# Controller2019_sensorless.net
KiCad netlist of a schematic drawn in EAGLE
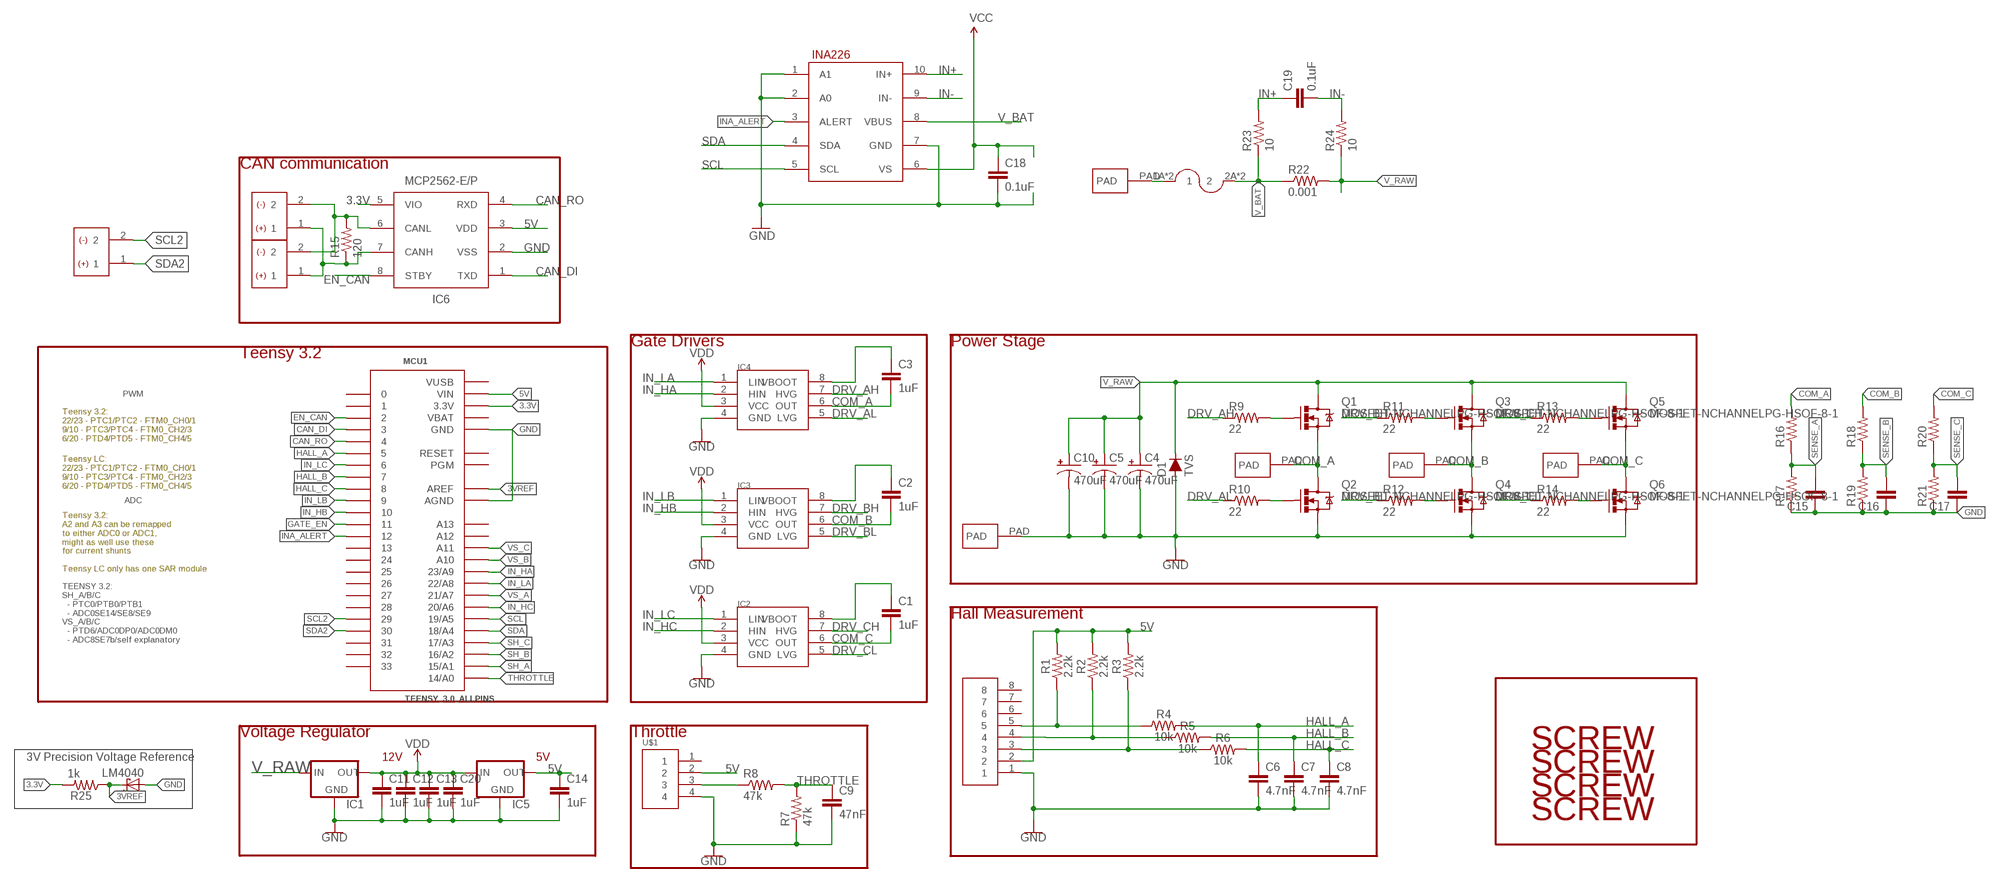
[diagram p0: schematic, sheet 1, part 1 of 2]
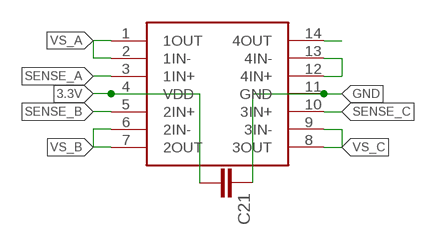
[diagram p1: schematic, sheet 1, part 2 of 2]

(export (version "E")
  (design (tool "Eeschema 10.0.6"))
  (components
    (comp (ref "C1")
      (value "1uF")
      (footprint "eagle-import:CAP-PTH-SMALL-KIT")
      (libsource (lib "eagle-import") (part "CAPKIT"))
    )
    (comp (ref "C2")
      (value "1uF")
      (footprint "eagle-import:CAP-PTH-SMALL-KIT")
      (libsource (lib "eagle-import") (part "CAPKIT"))
    )
    (comp (ref "C3")
      (value "1uF")
      (footprint "eagle-import:CAP-PTH-SMALL-KIT")
      (libsource (lib "eagle-import") (part "CAPKIT"))
    )
    (comp (ref "C4")
      (value "470uF")
      (footprint "eagle-import:CPOL-RADIAL-5MM-10MM")
      (libsource (lib "eagle-import") (part "1000UF-RADIAL-5MM-25V-20%"))
    )
    (comp (ref "C5")
      (value "470uF")
      (footprint "eagle-import:CPOL-RADIAL-5MM-10MM")
      (libsource (lib "eagle-import") (part "1000UF-RADIAL-5MM-25V-20%"))
    )
    (comp (ref "C6")
      (value "4.7nF")
      (footprint "eagle-import:0603-CAP")
      (libsource (lib "eagle-import") (part "SparkFun-Passives_CAP0603-CAP"))
    )
    (comp (ref "C7")
      (value "4.7nF")
      (footprint "eagle-import:0603-CAP")
      (libsource (lib "eagle-import") (part "SparkFun-Passives_CAP0603-CAP"))
    )
    (comp (ref "C8")
      (value "4.7nF")
      (footprint "eagle-import:0603-CAP")
      (libsource (lib "eagle-import") (part "SparkFun-Passives_CAP0603-CAP"))
    )
    (comp (ref "C9")
      (value "47nF")
      (footprint "eagle-import:0603-CAP")
      (libsource (lib "eagle-import") (part "SparkFun-Passives_CAP0603-CAP"))
    )
    (comp (ref "C10")
      (value "470uF")
      (footprint "eagle-import:CPOL-RADIAL-5MM-10MM")
      (libsource (lib "eagle-import") (part "1000UF-RADIAL-5MM-25V-20%"))
    )
    (comp (ref "C11")
      (value "1uF")
      (footprint "eagle-import:CAP-PTH-SMALL-KIT")
      (libsource (lib "eagle-import") (part "CAPKIT"))
    )
    (comp (ref "C12")
      (value "1uF")
      (footprint "eagle-import:CAP-PTH-SMALL-KIT")
      (libsource (lib "eagle-import") (part "CAPKIT"))
    )
    (comp (ref "C13")
      (value "1uF")
      (footprint "eagle-import:CAP-PTH-SMALL-KIT")
      (libsource (lib "eagle-import") (part "CAPKIT"))
    )
    (comp (ref "C14")
      (value "1uF")
      (footprint "eagle-import:CAP-PTH-SMALL-KIT")
      (libsource (lib "eagle-import") (part "CAPKIT"))
    )
    (comp (ref "C15")
      (value "CAP0603-CAP")
      (footprint "eagle-import:0603-CAP")
      (libsource (lib "eagle-import") (part "SparkFun-Passives_CAP0603-CAP"))
    )
    (comp (ref "C16")
      (value "CAP0603-CAP")
      (footprint "eagle-import:0603-CAP")
      (libsource (lib "eagle-import") (part "SparkFun-Passives_CAP0603-CAP"))
    )
    (comp (ref "C17")
      (value "CAP0603-CAP")
      (footprint "eagle-import:0603-CAP")
      (libsource (lib "eagle-import") (part "SparkFun-Passives_CAP0603-CAP"))
    )
    (comp (ref "C18")
      (value "0.1uF")
      (footprint "eagle-import:0603-CAP")
      (libsource (lib "eagle-import") (part "SparkFun-Passives_CAP0603-CAP"))
    )
    (comp (ref "C19")
      (value "0.1uF")
      (footprint "eagle-import:0603-CAP")
      (libsource (lib "eagle-import") (part "SparkFun-Passives_CAP0603-CAP"))
    )
    (comp (ref "C20")
      (value "1uF")
      (footprint "eagle-import:CAP-PTH-SMALL-KIT")
      (libsource (lib "eagle-import") (part "CAPKIT"))
    )
    (comp (ref "C21")
      (value "CAP0603-CAP")
      (footprint "eagle-import:0603-CAP")
      (libsource (lib "eagle-import") (part "SparkFun-Passives_CAP0603-CAP"))
    )
    (comp (ref "CAN1")
      (value "HEADER2")
      (footprint "eagle-import:2PINVALULOK")
      (libsource (lib "eagle-import") (part "HEADER2"))
    )
    (comp (ref "CAN2")
      (value "HEADER2")
      (footprint "eagle-import:2PINVALULOK")
      (libsource (lib "eagle-import") (part "HEADER2"))
    )
    (comp (ref "D1")
      (value "TVS")
      (footprint "eagle-import:DIODE-1N4001")
      (libsource (lib "eagle-import") (part "DIODE-PTH"))
    )
    (comp (ref "I2C")
      (value "HEADER2")
      (footprint "eagle-import:2PINVALULOK")
      (libsource (lib "eagle-import") (part "HEADER2"))
    )
    (comp (ref "IC1")
      (value "V_REG_78XX")
      (footprint "eagle-import:V78W_BACKWARDS")
      (libsource (lib "eagle-import") (part "V_REG_78XX"))
    )
    (comp (ref "IC2")
      (value "L6387EDIP8")
      (footprint "eagle-import:DIP762W53P254L1092H508Q8B")
      (libsource (lib "eagle-import") (part "L6387EDIP8"))
    )
    (comp (ref "IC3")
      (value "L6387EDIP8")
      (footprint "eagle-import:DIP762W53P254L1092H508Q8B")
      (libsource (lib "eagle-import") (part "L6387EDIP8"))
    )
    (comp (ref "IC4")
      (value "L6387EDIP8")
      (footprint "eagle-import:DIP762W53P254L1092H508Q8B")
      (libsource (lib "eagle-import") (part "L6387EDIP8"))
    )
    (comp (ref "IC5")
      (value "V_REG_78XXV78W")
      (footprint "eagle-import:V78W")
      (libsource (lib "eagle-import") (part "V_REG_78XXV78W"))
    )
    (comp (ref "IC6")
      (value "MCP2562-E/P")
      (footprint "eagle-import:PDIP8_300MC")
      (fields (field (name "MANUFACTURER_PART_NUMBER") "MCP2562EP"))
      (libsource (lib "eagle-import") (part "MCP2562-E/P"))
    )
    (comp (ref "IC7")
      (value "INA226")
      (footprint "eagle-import:PSOP-10")
      (libsource (lib "eagle-import") (part "INA226"))
    )
    (comp (ref "J3")
      (value "FUSE")
      (footprint "eagle-import:AUTO_FUSE")
      (libsource (lib "eagle-import") (part "FUSE"))
    )
    (comp (ref "MCU1")
      (value "TEENSY_3.0_ALLPINS")
      (footprint "eagle-import:TEENSY_3.0_ALLPINS")
      (libsource (lib "eagle-import") (part "TEENSY_3.0_ALLPINS"))
    )
    (comp (ref "Q1")
      (value "MOSFET-NCHANNELPG-HSOF-8-1")
      (footprint "eagle-import:PG-HSOF-8-1")
      (libsource (lib "eagle-import") (part "MOSFET-NCHANNELPG-HSOF-8-1"))
    )
    (comp (ref "Q2")
      (value "MOSFET-NCHANNELPG-HSOF-8-1")
      (footprint "eagle-import:PG-HSOF-8-1")
      (libsource (lib "eagle-import") (part "MOSFET-NCHANNELPG-HSOF-8-1"))
    )
    (comp (ref "Q3")
      (value "MOSFET-NCHANNELPG-HSOF-8-1")
      (footprint "eagle-import:PG-HSOF-8-1")
      (libsource (lib "eagle-import") (part "MOSFET-NCHANNELPG-HSOF-8-1"))
    )
    (comp (ref "Q4")
      (value "MOSFET-NCHANNELPG-HSOF-8-1")
      (footprint "eagle-import:PG-HSOF-8-1")
      (libsource (lib "eagle-import") (part "MOSFET-NCHANNELPG-HSOF-8-1"))
    )
    (comp (ref "Q5")
      (value "MOSFET-NCHANNELPG-HSOF-8-1")
      (footprint "eagle-import:PG-HSOF-8-1")
      (libsource (lib "eagle-import") (part "MOSFET-NCHANNELPG-HSOF-8-1"))
    )
    (comp (ref "Q6")
      (value "MOSFET-NCHANNELPG-HSOF-8-1")
      (footprint "eagle-import:PG-HSOF-8-1")
      (libsource (lib "eagle-import") (part "MOSFET-NCHANNELPG-HSOF-8-1"))
    )
    (comp (ref "R1")
      (value "2.2k")
      (footprint "eagle-import:0603")
      (libsource (lib "eagle-import") (part "SparkFun-Resistors_532_RESISTOR0603"))
    )
    (comp (ref "R2")
      (value "2.2k")
      (footprint "eagle-import:0603")
      (libsource (lib "eagle-import") (part "SparkFun-Resistors_532_RESISTOR0603"))
    )
    (comp (ref "R3")
      (value "2.2k")
      (footprint "eagle-import:0603")
      (libsource (lib "eagle-import") (part "SparkFun-Resistors_532_RESISTOR0603"))
    )
    (comp (ref "R4")
      (value "10k")
      (footprint "eagle-import:0603")
      (libsource (lib "eagle-import") (part "SparkFun-Resistors_532_RESISTOR0603"))
    )
    (comp (ref "R5")
      (value "10k")
      (footprint "eagle-import:0603")
      (libsource (lib "eagle-import") (part "SparkFun-Resistors_532_RESISTOR0603"))
    )
    (comp (ref "R6")
      (value "10k")
      (footprint "eagle-import:0603")
      (libsource (lib "eagle-import") (part "SparkFun-Resistors_532_RESISTOR0603"))
    )
    (comp (ref "R7")
      (value "47k")
      (footprint "eagle-import:0603-RES")
      (libsource (lib "eagle-import") (part "RESISTOR0603-RES"))
    )
    (comp (ref "R8")
      (value "47k")
      (footprint "eagle-import:0603-RES")
      (libsource (lib "eagle-import") (part "RESISTOR0603-RES"))
    )
    (comp (ref "R9")
      (value "22")
      (footprint "eagle-import:0603-RES")
      (libsource (lib "eagle-import") (part "RESISTOR0603-RES"))
    )
    (comp (ref "R10")
      (value "22")
      (footprint "eagle-import:0603-RES")
      (libsource (lib "eagle-import") (part "RESISTOR0603-RES"))
    )
    (comp (ref "R11")
      (value "22")
      (footprint "eagle-import:0603-RES")
      (libsource (lib "eagle-import") (part "RESISTOR0603-RES"))
    )
    (comp (ref "R12")
      (value "22")
      (footprint "eagle-import:0603-RES")
      (libsource (lib "eagle-import") (part "RESISTOR0603-RES"))
    )
    (comp (ref "R13")
      (value "22")
      (footprint "eagle-import:0603-RES")
      (libsource (lib "eagle-import") (part "RESISTOR0603-RES"))
    )
    (comp (ref "R14")
      (value "22")
      (footprint "eagle-import:0603-RES")
      (libsource (lib "eagle-import") (part "RESISTOR0603-RES"))
    )
    (comp (ref "R15")
      (value "120")
      (footprint "eagle-import:0603-RES")
      (libsource (lib "eagle-import") (part "RESISTOR0603-RES"))
    )
    (comp (ref "R16")
      (value "RESISTOR0603-RES")
      (footprint "eagle-import:0603-RES")
      (libsource (lib "eagle-import") (part "RESISTOR0603-RES"))
    )
    (comp (ref "R17")
      (value "RESISTOR0603-RES")
      (footprint "eagle-import:0603-RES")
      (libsource (lib "eagle-import") (part "RESISTOR0603-RES"))
    )
    (comp (ref "R18")
      (value "RESISTOR0603-RES")
      (footprint "eagle-import:0603-RES")
      (libsource (lib "eagle-import") (part "RESISTOR0603-RES"))
    )
    (comp (ref "R19")
      (value "RESISTOR0603-RES")
      (footprint "eagle-import:0603-RES")
      (libsource (lib "eagle-import") (part "RESISTOR0603-RES"))
    )
    (comp (ref "R20")
      (value "RESISTOR0603-RES")
      (footprint "eagle-import:0603-RES")
      (libsource (lib "eagle-import") (part "RESISTOR0603-RES"))
    )
    (comp (ref "R21")
      (value "RESISTOR0603-RES")
      (footprint "eagle-import:0603-RES")
      (libsource (lib "eagle-import") (part "RESISTOR0603-RES"))
    )
    (comp (ref "R22")
      (value "0.001")
      (footprint "eagle-import:R2512")
      (libsource (lib "eagle-import") (part "SparkFun-Resistors_RESISTOR2512"))
    )
    (comp (ref "R23")
      (value "10")
      (footprint "eagle-import:0603-RES")
      (libsource (lib "eagle-import") (part "RESISTOR0603-RES"))
    )
    (comp (ref "R24")
      (value "10")
      (footprint "eagle-import:0603-RES")
      (libsource (lib "eagle-import") (part "RESISTOR0603-RES"))
    )
    (comp (ref "R25")
      (value "1k")
      (footprint "eagle-import:0603-RES")
      (libsource (lib "eagle-import") (part "RESISTOR0603-RES"))
    )
    (comp (ref "U$1")
      (value "HEADER4VALULOK")
      (footprint "eagle-import:4PINVALULOK")
      (libsource (lib "eagle-import") (part "HEADER4VALULOK"))
    )
    (comp (ref "U$2")
      (value "OPAMP_QUAD")
      (footprint "eagle-import:TSSOP-14")
      (libsource (lib "eagle-import") (part "OPAMP_QUAD"))
    )
    (comp (ref "U$4")
      (value "PAD")
      (footprint "eagle-import:PAD")
      (libsource (lib "eagle-import") (part "PAD"))
    )
    (comp (ref "U$5")
      (value "PAD")
      (footprint "eagle-import:PAD")
      (libsource (lib "eagle-import") (part "PAD"))
    )
    (comp (ref "U$6")
      (value "PAD")
      (footprint "eagle-import:PAD")
      (libsource (lib "eagle-import") (part "PAD"))
    )
    (comp (ref "U$7")
      (value "PAD")
      (footprint "eagle-import:PAD")
      (libsource (lib "eagle-import") (part "PAD"))
    )
    (comp (ref "U$8")
      (value "PAD")
      (footprint "eagle-import:PAD")
      (libsource (lib "eagle-import") (part "PAD"))
    )
    (comp (ref "U$10")
      (value "SCREW")
      (footprint "eagle-import:M3HOLE")
      (libsource (lib "eagle-import") (part "SCREW"))
    )
    (comp (ref "U$11")
      (value "SCREW")
      (footprint "eagle-import:M3HOLE")
      (libsource (lib "eagle-import") (part "SCREW"))
    )
    (comp (ref "U$12")
      (value "SCREW")
      (footprint "eagle-import:M3HOLE")
      (libsource (lib "eagle-import") (part "SCREW"))
    )
    (comp (ref "U$13")
      (value "SCREW")
      (footprint "eagle-import:M3HOLE")
      (libsource (lib "eagle-import") (part "SCREW"))
    )
    (comp (ref "U$14")
      (value "HEADER8")
      (footprint "eagle-import:8PINVALULOK")
      (libsource (lib "eagle-import") (part "HEADER8"))
    )
    (comp (ref "U$15")
      (value "LM4040")
      (footprint "eagle-import:SOT23-3")
      (libsource (lib "eagle-import") (part "LM4040"))
    )
  )
  (nets
    (net (code "1") (name "/DRV_AH") (class "Default")
      (node (ref "IC4") (pin "7") (pinfunction "HVG_7") (pintype "bidirectional"))
      (node (ref "R9") (pin "1") (pinfunction "1_1") (pintype "passive"))
    )
    (net (code "2") (name "/DRV_AL") (class "Default")
      (node (ref "IC4") (pin "5") (pinfunction "LVG_5") (pintype "bidirectional"))
      (node (ref "R10") (pin "1") (pinfunction "1_1") (pintype "passive"))
    )
    (net (code "3") (name "/DRV_BH") (class "Default")
      (node (ref "IC3") (pin "7") (pinfunction "HVG_7") (pintype "bidirectional"))
      (node (ref "R11") (pin "1") (pinfunction "1_1") (pintype "passive"))
    )
    (net (code "4") (name "/DRV_BL") (class "Default")
      (node (ref "IC3") (pin "5") (pinfunction "LVG_5") (pintype "bidirectional"))
      (node (ref "R12") (pin "1") (pinfunction "1_1") (pintype "passive"))
    )
    (net (code "5") (name "/DRV_CH") (class "Default")
      (node (ref "IC2") (pin "7") (pinfunction "HVG_7") (pintype "bidirectional"))
      (node (ref "R13") (pin "1") (pinfunction "1_1") (pintype "passive"))
    )
    (net (code "6") (name "/DRV_CL") (class "Default")
      (node (ref "IC2") (pin "5") (pinfunction "LVG_5") (pintype "bidirectional"))
      (node (ref "R14") (pin "1") (pinfunction "1_1") (pintype "passive"))
    )
    (net (code "7") (name "/IN+") (class "Default")
      (node (ref "C19") (pin "1") (pinfunction "1_1") (pintype "passive"))
      (node (ref "IC7") (pin "10") (pinfunction "IN+_10") (pintype "bidirectional"))
      (node (ref "R23") (pin "2") (pinfunction "2_2") (pintype "passive"))
    )
    (net (code "8") (name "/IN-") (class "Default")
      (node (ref "C19") (pin "2") (pinfunction "2_2") (pintype "passive"))
      (node (ref "IC7") (pin "9") (pinfunction "IN-_9") (pintype "bidirectional"))
      (node (ref "R24") (pin "2") (pinfunction "2_2") (pintype "passive"))
    )
    (net (code "9") (name "/VBAT") (class "Default")
      (node (ref "MCU1") (pin "VBAT") (pinfunction "VBAT_VBAT") (pintype "power_in"))
    )
    (net (code "10") (name "/VUSB") (class "Default")
      (node (ref "MCU1") (pin "VUSB") (pinfunction "VUSB_VUSB") (pintype "power_in"))
    )
    (net (code "11") (name "3.3V") (class "Default")
      (node (ref "C21") (pin "2") (pinfunction "2_2") (pintype "passive"))
      (node (ref "IC6") (pin "5") (pinfunction "VIO_5") (pintype "passive"))
      (node (ref "MCU1") (pin "3.3V") (pinfunction "3.3V_3.3V") (pintype "power_in"))
      (node (ref "MCU1") (pin "3.3V1") (pinfunction "3.3V_3.3V1") (pintype "power_in"))
      (node (ref "MCU1") (pin "3.3V2") (pinfunction "3.3V_3.3V2") (pintype "power_in"))
      (node (ref "R25") (pin "2") (pinfunction "2_2") (pintype "passive"))
      (node (ref "U$2") (pin "4") (pinfunction "VDD_4") (pintype "bidirectional"))
    )
    (net (code "12") (name "3VREF") (class "Default")
      (node (ref "MCU1") (pin "AREF") (pinfunction "AREF_AREF") (pintype "power_in"))
      (node (ref "R25") (pin "1") (pinfunction "1_1") (pintype "passive"))
      (node (ref "U$15") (pin "1") (pinfunction "C_1") (pintype "passive"))
    )
    (net (code "13") (name "5V") (class "Default")
      (node (ref "C14") (pin "1") (pinfunction "1_1") (pintype "passive"))
      (node (ref "IC5") (pin "OUT") (pinfunction "OUT_OUT") (pintype "output"))
      (node (ref "IC6") (pin "3") (pinfunction "VDD_3") (pintype "power_in"))
      (node (ref "MCU1") (pin "VIN") (pinfunction "VIN_VIN") (pintype "power_in"))
      (node (ref "R1") (pin "2") (pinfunction "2_2") (pintype "passive"))
      (node (ref "R2") (pin "2") (pinfunction "2_2") (pintype "passive"))
      (node (ref "R3") (pin "2") (pinfunction "2_2") (pintype "passive"))
      (node (ref "U$1") (pin "2") (pinfunction "2_2") (pintype "bidirectional"))
      (node (ref "U$14") (pin "2") (pinfunction "2_2") (pintype "bidirectional"))
    )
    (net (code "14") (name "CAN_DI") (class "Default")
      (node (ref "IC6") (pin "1") (pinfunction "TXD_1") (pintype "input"))
      (node (ref "MCU1") (pin "3") (pinfunction "3_3") (pintype "bidirectional"))
    )
    (net (code "15") (name "CAN_RO") (class "Default")
      (node (ref "IC6") (pin "4") (pinfunction "RXD_4") (pintype "output"))
      (node (ref "MCU1") (pin "4") (pinfunction "4_4") (pintype "bidirectional"))
    )
    (net (code "16") (name "COM_A") (class "Default")
      (node (ref "C3") (pin "2") (pinfunction "2_2") (pintype "passive"))
      (node (ref "IC4") (pin "6") (pinfunction "OUT_6") (pintype "bidirectional"))
      (node (ref "Q1") (pin "S") (pinfunction "S_S") (pintype "passive"))
      (node (ref "Q2") (pin "D") (pinfunction "D_D") (pintype "passive"))
      (node (ref "R16") (pin "2") (pinfunction "2_2") (pintype "passive"))
      (node (ref "U$6") (pin "PAD") (pinfunction "PAD_PAD") (pintype "bidirectional"))
    )
    (net (code "17") (name "COM_B") (class "Default")
      (node (ref "C2") (pin "2") (pinfunction "2_2") (pintype "passive"))
      (node (ref "IC3") (pin "6") (pinfunction "OUT_6") (pintype "bidirectional"))
      (node (ref "Q3") (pin "S") (pinfunction "S_S") (pintype "passive"))
      (node (ref "Q4") (pin "D") (pinfunction "D_D") (pintype "passive"))
      (node (ref "R18") (pin "2") (pinfunction "2_2") (pintype "passive"))
      (node (ref "U$7") (pin "PAD") (pinfunction "PAD_PAD") (pintype "bidirectional"))
    )
    (net (code "18") (name "COM_C") (class "Default")
      (node (ref "C1") (pin "2") (pinfunction "2_2") (pintype "passive"))
      (node (ref "IC2") (pin "6") (pinfunction "OUT_6") (pintype "bidirectional"))
      (node (ref "Q5") (pin "S") (pinfunction "S_S") (pintype "passive"))
      (node (ref "Q6") (pin "D") (pinfunction "D_D") (pintype "passive"))
      (node (ref "R20") (pin "2") (pinfunction "2_2") (pintype "passive"))
      (node (ref "U$8") (pin "PAD") (pinfunction "PAD_PAD") (pintype "bidirectional"))
    )
    (net (code "19") (name "EN_CAN") (class "Default")
      (node (ref "IC6") (pin "8") (pinfunction "STBY_8") (pintype "input"))
      (node (ref "MCU1") (pin "2") (pinfunction "2_2") (pintype "bidirectional"))
    )
    (net (code "20") (name "GATE_EN") (class "Default")
      (node (ref "MCU1") (pin "11") (pinfunction "11_11") (pintype "bidirectional"))
    )
    (net (code "21") (name "GND") (class "Default")
      (node (ref "C10") (pin "-") (pinfunction "-_-") (pintype "passive"))
      (node (ref "C11") (pin "2") (pinfunction "2_2") (pintype "passive"))
      (node (ref "C12") (pin "2") (pinfunction "2_2") (pintype "passive"))
      (node (ref "C13") (pin "2") (pinfunction "2_2") (pintype "passive"))
      (node (ref "C14") (pin "2") (pinfunction "2_2") (pintype "passive"))
      (node (ref "C15") (pin "1") (pinfunction "1_1") (pintype "passive"))
      (node (ref "C16") (pin "1") (pinfunction "1_1") (pintype "passive"))
      (node (ref "C17") (pin "1") (pinfunction "1_1") (pintype "passive"))
      (node (ref "C18") (pin "2") (pinfunction "2_2") (pintype "passive"))
      (node (ref "C20") (pin "2") (pinfunction "2_2") (pintype "passive"))
      (node (ref "C21") (pin "1") (pinfunction "1_1") (pintype "passive"))
      (node (ref "C4") (pin "-") (pinfunction "-_-") (pintype "passive"))
      (node (ref "C5") (pin "-") (pinfunction "-_-") (pintype "passive"))
      (node (ref "C6") (pin "2") (pinfunction "2_2") (pintype "passive"))
      (node (ref "C7") (pin "2") (pinfunction "2_2") (pintype "passive"))
      (node (ref "C8") (pin "2") (pinfunction "2_2") (pintype "passive"))
      (node (ref "C9") (pin "2") (pinfunction "2_2") (pintype "passive"))
      (node (ref "D1") (pin "A") (pinfunction "A_A") (pintype "passive"))
      (node (ref "IC1") (pin "GND") (pinfunction "GND_GND") (pintype "input"))
      (node (ref "IC2") (pin "4") (pinfunction "GND_4") (pintype "bidirectional"))
      (node (ref "IC3") (pin "4") (pinfunction "GND_4") (pintype "bidirectional"))
      (node (ref "IC4") (pin "4") (pinfunction "GND_4") (pintype "bidirectional"))
      (node (ref "IC5") (pin "GND") (pinfunction "GND_GND") (pintype "input"))
      (node (ref "IC6") (pin "2") (pinfunction "VSS_2") (pintype "power_in"))
      (node (ref "IC7") (pin "1") (pinfunction "A1_1") (pintype "bidirectional"))
      (node (ref "IC7") (pin "2") (pinfunction "A0_2") (pintype "bidirectional"))
      (node (ref "IC7") (pin "7") (pinfunction "GND_7") (pintype "bidirectional"))
      (node (ref "MCU1") (pin "AGND") (pinfunction "AGND_AGND") (pintype "power_in"))
      (node (ref "MCU1") (pin "GND") (pinfunction "GND_GND") (pintype "power_in"))
      (node (ref "MCU1") (pin "GND1") (pinfunction "GND_GND1") (pintype "power_in"))
      (node (ref "MCU1") (pin "GND2") (pinfunction "GND_GND2") (pintype "power_in"))
      (node (ref "Q2") (pin "S") (pinfunction "S_S") (pintype "passive"))
      (node (ref "Q4") (pin "S") (pinfunction "S_S") (pintype "passive"))
      (node (ref "Q6") (pin "S") (pinfunction "S_S") (pintype "passive"))
      (node (ref "R17") (pin "1") (pinfunction "1_1") (pintype "passive"))
      (node (ref "R19") (pin "1") (pinfunction "1_1") (pintype "passive"))
      (node (ref "R21") (pin "1") (pinfunction "1_1") (pintype "passive"))
      (node (ref "R7") (pin "1") (pinfunction "1_1") (pintype "passive"))
      (node (ref "U$1") (pin "4") (pinfunction "4_4") (pintype "bidirectional"))
      (node (ref "U$14") (pin "1") (pinfunction "1_1") (pintype "bidirectional"))
      (node (ref "U$15") (pin "2") (pinfunction "A_2") (pintype "passive"))
      (node (ref "U$2") (pin "11") (pinfunction "GND_11") (pintype "bidirectional"))
      (node (ref "U$5") (pin "PAD") (pinfunction "PAD_PAD") (pintype "bidirectional"))
    )
    (net (code "22") (name "HALL_A") (class "Default")
      (node (ref "C6") (pin "1") (pinfunction "1_1") (pintype "passive"))
      (node (ref "MCU1") (pin "5") (pinfunction "5_5") (pintype "bidirectional"))
      (node (ref "R4") (pin "2") (pinfunction "2_2") (pintype "passive"))
    )
    (net (code "23") (name "HALL_B") (class "Default")
      (node (ref "C7") (pin "1") (pinfunction "1_1") (pintype "passive"))
      (node (ref "MCU1") (pin "7") (pinfunction "7_7") (pintype "bidirectional"))
      (node (ref "R5") (pin "2") (pinfunction "2_2") (pintype "passive"))
    )
    (net (code "24") (name "HALL_C") (class "Default")
      (node (ref "C8") (pin "1") (pinfunction "1_1") (pintype "passive"))
      (node (ref "MCU1") (pin "8") (pinfunction "8_8") (pintype "bidirectional"))
      (node (ref "R6") (pin "2") (pinfunction "2_2") (pintype "passive"))
    )
    (net (code "25") (name "INA_ALERT") (class "Default")
      (node (ref "IC7") (pin "3") (pinfunction "ALERT_3") (pintype "bidirectional"))
      (node (ref "MCU1") (pin "12") (pinfunction "12_12") (pintype "bidirectional"))
    )
    (net (code "26") (name "IN_HA") (class "Default")
      (node (ref "IC4") (pin "2") (pinfunction "HIN_2") (pintype "bidirectional"))
      (node (ref "MCU1") (pin "23/A9") (pinfunction "23/A9_23/A9") (pintype "bidirectional"))
    )
    (net (code "27") (name "IN_HB") (class "Default")
      (node (ref "IC3") (pin "2") (pinfunction "HIN_2") (pintype "bidirectional"))
      (node (ref "MCU1") (pin "10") (pinfunction "10_10") (pintype "bidirectional"))
    )
    (net (code "28") (name "IN_HC") (class "Default")
      (node (ref "IC2") (pin "2") (pinfunction "HIN_2") (pintype "bidirectional"))
      (node (ref "MCU1") (pin "20/A6") (pinfunction "20/A6_20/A6") (pintype "bidirectional"))
    )
    (net (code "29") (name "IN_LA") (class "Default")
      (node (ref "IC4") (pin "1") (pinfunction "LIN_1") (pintype "bidirectional"))
      (node (ref "MCU1") (pin "22/A8") (pinfunction "22/A8_22/A8") (pintype "bidirectional"))
    )
    (net (code "30") (name "IN_LB") (class "Default")
      (node (ref "IC3") (pin "1") (pinfunction "LIN_1") (pintype "bidirectional"))
      (node (ref "MCU1") (pin "9") (pinfunction "9_9") (pintype "bidirectional"))
    )
    (net (code "31") (name "IN_LC") (class "Default")
      (node (ref "IC2") (pin "1") (pinfunction "LIN_1") (pintype "bidirectional"))
      (node (ref "MCU1") (pin "6") (pinfunction "6_6") (pintype "bidirectional"))
    )
    (net (code "32") (name "Net-(IC2-VBOOT)") (class "Default")
      (node (ref "C1") (pin "1") (pinfunction "1_1") (pintype "passive"))
      (node (ref "IC2") (pin "8") (pinfunction "VBOOT_8") (pintype "bidirectional"))
    )
    (net (code "33") (name "Net-(IC3-VBOOT)") (class "Default")
      (node (ref "C2") (pin "1") (pinfunction "1_1") (pintype "passive"))
      (node (ref "IC3") (pin "8") (pinfunction "VBOOT_8") (pintype "bidirectional"))
    )
    (net (code "34") (name "Net-(IC4-VBOOT)") (class "Default")
      (node (ref "C3") (pin "1") (pinfunction "1_1") (pintype "passive"))
      (node (ref "IC4") (pin "8") (pinfunction "VBOOT_8") (pintype "bidirectional"))
    )
    (net (code "35") (name "Net-(IC6-CANH)") (class "Default")
      (node (ref "CAN1") (pin "1") (pinfunction "1_1") (pintype "bidirectional"))
      (node (ref "CAN2") (pin "1") (pinfunction "1_1") (pintype "bidirectional"))
      (node (ref "IC6") (pin "7") (pinfunction "CANH_7") (pintype "bidirectional"))
      (node (ref "R15") (pin "1") (pinfunction "1_1") (pintype "passive"))
    )
    (net (code "36") (name "Net-(IC6-CANL)") (class "Default")
      (node (ref "CAN1") (pin "2") (pinfunction "2_2") (pintype "bidirectional"))
      (node (ref "CAN2") (pin "2") (pinfunction "2_2") (pintype "bidirectional"))
      (node (ref "IC6") (pin "6") (pinfunction "CANL_6") (pintype "bidirectional"))
      (node (ref "R15") (pin "2") (pinfunction "2_2") (pintype "passive"))
    )
    (net (code "37") (name "Net-(J3-1-Pad1A)") (class "Default")
      (node (ref "J3") (pin "1A") (pinfunction "1_1A") (pintype "bidirectional"))
      (node (ref "J3") (pin "1B") (pinfunction "1_1B") (pintype "bidirectional"))
      (node (ref "U$4") (pin "PAD") (pinfunction "PAD_PAD") (pintype "bidirectional"))
    )
    (net (code "38") (name "Net-(Q1-PadG)") (class "Default")
      (node (ref "Q1") (pin "G") (pinfunction "G_G") (pintype "passive"))
      (node (ref "R9") (pin "2") (pinfunction "2_2") (pintype "passive"))
    )
    (net (code "39") (name "Net-(Q2-PadG)") (class "Default")
      (node (ref "Q2") (pin "G") (pinfunction "G_G") (pintype "passive"))
      (node (ref "R10") (pin "2") (pinfunction "2_2") (pintype "passive"))
    )
    (net (code "40") (name "Net-(Q3-PadG)") (class "Default")
      (node (ref "Q3") (pin "G") (pinfunction "G_G") (pintype "passive"))
      (node (ref "R11") (pin "2") (pinfunction "2_2") (pintype "passive"))
    )
    (net (code "41") (name "Net-(Q4-PadG)") (class "Default")
      (node (ref "Q4") (pin "G") (pinfunction "G_G") (pintype "passive"))
      (node (ref "R12") (pin "2") (pinfunction "2_2") (pintype "passive"))
    )
    (net (code "42") (name "Net-(Q5-PadG)") (class "Default")
      (node (ref "Q5") (pin "G") (pinfunction "G_G") (pintype "passive"))
      (node (ref "R13") (pin "2") (pinfunction "2_2") (pintype "passive"))
    )
    (net (code "43") (name "Net-(Q6-PadG)") (class "Default")
      (node (ref "Q6") (pin "G") (pinfunction "G_G") (pintype "passive"))
      (node (ref "R14") (pin "2") (pinfunction "2_2") (pintype "passive"))
    )
    (net (code "44") (name "Net-(R1-Pad1)") (class "Default")
      (node (ref "R1") (pin "1") (pinfunction "1_1") (pintype "passive"))
      (node (ref "R4") (pin "1") (pinfunction "1_1") (pintype "passive"))
      (node (ref "U$14") (pin "5") (pinfunction "5_5") (pintype "bidirectional"))
    )
    (net (code "45") (name "Net-(R2-Pad1)") (class "Default")
      (node (ref "R2") (pin "1") (pinfunction "1_1") (pintype "passive"))
      (node (ref "R5") (pin "1") (pinfunction "1_1") (pintype "passive"))
      (node (ref "U$14") (pin "4") (pinfunction "4_4") (pintype "bidirectional"))
    )
    (net (code "46") (name "Net-(R3-Pad1)") (class "Default")
      (node (ref "R3") (pin "1") (pinfunction "1_1") (pintype "passive"))
      (node (ref "R6") (pin "1") (pinfunction "1_1") (pintype "passive"))
      (node (ref "U$14") (pin "3") (pinfunction "3_3") (pintype "bidirectional"))
    )
    (net (code "47") (name "Net-(R8-Pad1)") (class "Default")
      (node (ref "R8") (pin "1") (pinfunction "1_1") (pintype "passive"))
      (node (ref "U$1") (pin "3") (pinfunction "3_3") (pintype "bidirectional"))
    )
    (net (code "48") (name "Net-(U$2-4IN+)") (class "Default")
      (node (ref "U$2") (pin "12") (pinfunction "4IN+_12") (pintype "bidirectional"))
      (node (ref "U$2") (pin "13") (pinfunction "4IN-_13") (pintype "bidirectional"))
    )
    (net (code "49") (name "SCL") (class "Default")
      (node (ref "IC7") (pin "5") (pinfunction "SCL_5") (pintype "bidirectional"))
      (node (ref "MCU1") (pin "19/A5") (pinfunction "19/A5_19/A5") (pintype "bidirectional"))
    )
    (net (code "50") (name "SCL2") (class "Default")
      (node (ref "I2C") (pin "2") (pinfunction "2_2") (pintype "bidirectional"))
      (node (ref "MCU1") (pin "29") (pinfunction "29_29") (pintype "bidirectional"))
    )
    (net (code "51") (name "SDA") (class "Default")
      (node (ref "IC7") (pin "4") (pinfunction "SDA_4") (pintype "bidirectional"))
      (node (ref "MCU1") (pin "18/A4") (pinfunction "18/A4_18/A4") (pintype "bidirectional"))
    )
    (net (code "52") (name "SDA2") (class "Default")
      (node (ref "I2C") (pin "1") (pinfunction "1_1") (pintype "bidirectional"))
      (node (ref "MCU1") (pin "30") (pinfunction "30_30") (pintype "bidirectional"))
    )
    (net (code "53") (name "SENSE_A") (class "Default")
      (node (ref "C15") (pin "2") (pinfunction "2_2") (pintype "passive"))
      (node (ref "R16") (pin "1") (pinfunction "1_1") (pintype "passive"))
      (node (ref "R17") (pin "2") (pinfunction "2_2") (pintype "passive"))
      (node (ref "U$2") (pin "3") (pinfunction "1IN+_3") (pintype "bidirectional"))
    )
    (net (code "54") (name "SENSE_B") (class "Default")
      (node (ref "C16") (pin "2") (pinfunction "2_2") (pintype "passive"))
      (node (ref "R18") (pin "1") (pinfunction "1_1") (pintype "passive"))
      (node (ref "R19") (pin "2") (pinfunction "2_2") (pintype "passive"))
      (node (ref "U$2") (pin "5") (pinfunction "2IN+_5") (pintype "bidirectional"))
    )
    (net (code "55") (name "SENSE_C") (class "Default")
      (node (ref "C17") (pin "2") (pinfunction "2_2") (pintype "passive"))
      (node (ref "R20") (pin "1") (pinfunction "1_1") (pintype "passive"))
      (node (ref "R21") (pin "2") (pinfunction "2_2") (pintype "passive"))
      (node (ref "U$2") (pin "10") (pinfunction "3IN+_10") (pintype "bidirectional"))
    )
    (net (code "56") (name "SH_A") (class "Default")
      (node (ref "MCU1") (pin "15/A1") (pinfunction "15/A1_15/A1") (pintype "bidirectional"))
    )
    (net (code "57") (name "SH_B") (class "Default")
      (node (ref "MCU1") (pin "16/A2") (pinfunction "16/A2_16/A2") (pintype "bidirectional"))
    )
    (net (code "58") (name "SH_C") (class "Default")
      (node (ref "MCU1") (pin "17/A3") (pinfunction "17/A3_17/A3") (pintype "bidirectional"))
    )
    (net (code "59") (name "THROTTLE") (class "Default")
      (node (ref "C9") (pin "1") (pinfunction "1_1") (pintype "passive"))
      (node (ref "MCU1") (pin "14/A0") (pinfunction "14/A0_14/A0") (pintype "bidirectional"))
      (node (ref "R7") (pin "2") (pinfunction "2_2") (pintype "passive"))
      (node (ref "R8") (pin "2") (pinfunction "2_2") (pintype "passive"))
    )
    (net (code "60") (name "VCC") (class "Default")
      (node (ref "C18") (pin "1") (pinfunction "1_1") (pintype "passive"))
      (node (ref "IC7") (pin "6") (pinfunction "VS_6") (pintype "bidirectional"))
    )
    (net (code "61") (name "VDD") (class "Default")
      (node (ref "C11") (pin "1") (pinfunction "1_1") (pintype "passive"))
      (node (ref "C12") (pin "1") (pinfunction "1_1") (pintype "passive"))
      (node (ref "C13") (pin "1") (pinfunction "1_1") (pintype "passive"))
      (node (ref "C20") (pin "1") (pinfunction "1_1") (pintype "passive"))
      (node (ref "IC1") (pin "OUT") (pinfunction "OUT_OUT") (pintype "output"))
      (node (ref "IC2") (pin "3") (pinfunction "VCC_3") (pintype "bidirectional"))
      (node (ref "IC3") (pin "3") (pinfunction "VCC_3") (pintype "bidirectional"))
      (node (ref "IC4") (pin "3") (pinfunction "VCC_3") (pintype "bidirectional"))
      (node (ref "IC5") (pin "IN") (pinfunction "IN_IN") (pintype "input"))
    )
    (net (code "62") (name "VS_A") (class "Default")
      (node (ref "MCU1") (pin "21/A7") (pinfunction "21/A7_21/A7") (pintype "bidirectional"))
      (node (ref "U$2") (pin "1") (pinfunction "1OUT_1") (pintype "bidirectional"))
      (node (ref "U$2") (pin "2") (pinfunction "1IN-_2") (pintype "bidirectional"))
    )
    (net (code "63") (name "VS_B") (class "Default")
      (node (ref "MCU1") (pin "A10") (pinfunction "A10_A10") (pintype "bidirectional"))
      (node (ref "U$2") (pin "6") (pinfunction "2IN-_6") (pintype "bidirectional"))
      (node (ref "U$2") (pin "7") (pinfunction "2OUT_7") (pintype "bidirectional"))
    )
    (net (code "64") (name "VS_C") (class "Default")
      (node (ref "MCU1") (pin "A11") (pinfunction "A11_A11") (pintype "bidirectional"))
      (node (ref "U$2") (pin "8") (pinfunction "3OUT_8") (pintype "bidirectional"))
      (node (ref "U$2") (pin "9") (pinfunction "3IN-_9") (pintype "bidirectional"))
    )
    (net (code "65") (name "V_BAT") (class "Default")
      (node (ref "IC7") (pin "8") (pinfunction "VBUS_8") (pintype "bidirectional"))
      (node (ref "J3") (pin "2A") (pinfunction "2_2A") (pintype "bidirectional"))
      (node (ref "J3") (pin "2B") (pinfunction "2_2B") (pintype "bidirectional"))
      (node (ref "R22") (pin "1") (pinfunction "1_1") (pintype "passive"))
      (node (ref "R23") (pin "1") (pinfunction "1_1") (pintype "passive"))
    )
    (net (code "66") (name "V_RAW") (class "Default")
      (node (ref "C10") (pin "+") (pinfunction "+_+") (pintype "passive"))
      (node (ref "C4") (pin "+") (pinfunction "+_+") (pintype "passive"))
      (node (ref "C5") (pin "+") (pinfunction "+_+") (pintype "passive"))
      (node (ref "D1") (pin "C") (pinfunction "C_C") (pintype "passive"))
      (node (ref "IC1") (pin "IN") (pinfunction "IN_IN") (pintype "input"))
      (node (ref "Q1") (pin "D") (pinfunction "D_D") (pintype "passive"))
      (node (ref "Q3") (pin "D") (pinfunction "D_D") (pintype "passive"))
      (node (ref "Q5") (pin "D") (pinfunction "D_D") (pintype "passive"))
      (node (ref "R22") (pin "2") (pinfunction "2_2") (pintype "passive"))
      (node (ref "R24") (pin "1") (pinfunction "1_1") (pintype "passive"))
    )
    (net (code "67") (name "unconnected-(MCU1-Pad0)") (class "Default")
      (node (ref "MCU1") (pin "0") (pinfunction "0_0") (pintype "bidirectional"))
    )
    (net (code "68") (name "unconnected-(MCU1-Pad1)") (class "Default")
      (node (ref "MCU1") (pin "1") (pinfunction "1_1") (pintype "bidirectional"))
    )
    (net (code "69") (name "unconnected-(MCU1-Pad13)") (class "Default")
      (node (ref "MCU1") (pin "13") (pinfunction "13_13") (pintype "bidirectional"))
    )
    (net (code "70") (name "unconnected-(MCU1-Pad24)") (class "Default")
      (node (ref "MCU1") (pin "24") (pinfunction "24_24") (pintype "bidirectional"))
    )
    (net (code "71") (name "unconnected-(MCU1-Pad25)") (class "Default")
      (node (ref "MCU1") (pin "25") (pinfunction "25_25") (pintype "bidirectional"))
    )
    (net (code "72") (name "unconnected-(MCU1-Pad26)") (class "Default")
      (node (ref "MCU1") (pin "26") (pinfunction "26_26") (pintype "bidirectional"))
    )
    (net (code "73") (name "unconnected-(MCU1-Pad27)") (class "Default")
      (node (ref "MCU1") (pin "27") (pinfunction "27_27") (pintype "bidirectional"))
    )
    (net (code "74") (name "unconnected-(MCU1-Pad28)") (class "Default")
      (node (ref "MCU1") (pin "28") (pinfunction "28_28") (pintype "bidirectional"))
    )
    (net (code "75") (name "unconnected-(MCU1-Pad31)") (class "Default")
      (node (ref "MCU1") (pin "31") (pinfunction "31_31") (pintype "bidirectional"))
    )
    (net (code "76") (name "unconnected-(MCU1-Pad32)") (class "Default")
      (node (ref "MCU1") (pin "32") (pinfunction "32_32") (pintype "bidirectional"))
    )
    (net (code "77") (name "unconnected-(MCU1-Pad33)") (class "Default")
      (node (ref "MCU1") (pin "33") (pinfunction "33_33") (pintype "bidirectional"))
    )
    (net (code "78") (name "unconnected-(MCU1-PadA12)") (class "Default")
      (node (ref "MCU1") (pin "A12") (pinfunction "A12_A12") (pintype "bidirectional"))
    )
    (net (code "79") (name "unconnected-(MCU1-PadA13)") (class "Default")
      (node (ref "MCU1") (pin "A13") (pinfunction "A13_A13") (pintype "bidirectional"))
    )
    (net (code "80") (name "unconnected-(MCU1-PadPGM)") (class "Default")
      (node (ref "MCU1") (pin "PGM") (pinfunction "PGM_PGM") (pintype "bidirectional"))
    )
    (net (code "81") (name "unconnected-(MCU1-PadRESET)") (class "Default")
      (node (ref "MCU1") (pin "RESET") (pinfunction "RESET_RESET") (pintype "bidirectional"))
    )
    (net (code "82") (name "unconnected-(U$1-Pad1)") (class "Default")
      (node (ref "U$1") (pin "1") (pinfunction "1_1") (pintype "bidirectional"))
    )
    (net (code "83") (name "unconnected-(U$2-4OUT-Pad14)") (class "Default")
      (node (ref "U$2") (pin "14") (pinfunction "4OUT_14") (pintype "bidirectional"))
    )
    (net (code "84") (name "unconnected-(U$14-Pad6)") (class "Default")
      (node (ref "U$14") (pin "6") (pinfunction "6_6") (pintype "bidirectional"))
    )
    (net (code "85") (name "unconnected-(U$14-Pad7)") (class "Default")
      (node (ref "U$14") (pin "7") (pinfunction "7_7") (pintype "bidirectional"))
    )
    (net (code "86") (name "unconnected-(U$14-Pad8)") (class "Default")
      (node (ref "U$14") (pin "8") (pinfunction "8_8") (pintype "bidirectional"))
    )
  )
)
